# 6_LED_INTERFACE_SFP.net
KiCad netlist of a schematic drawn in Altium Designer
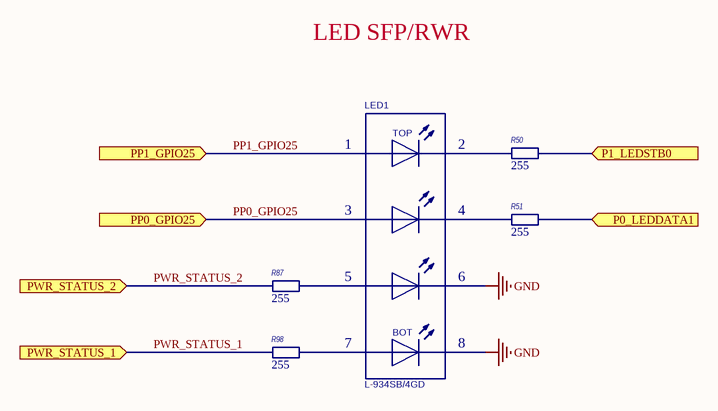
[diagram p0: 6_LED INTERFACE SFP.SchDoc]

(export (version "E")
  (design (tool "Eeschema 10.0.6"))
  (components
    (comp (ref "LED1")
      (value "L-934SB/4GD")
      (footprint "L-934SB/4GD")
      (description "4 LED Green L-934SB/4GD")
      (fields
        (field (name "CUSTOMER PART NUMBER") "Светодиод, 4 LED Green L-934SB/4GD QUAD-LEVEL LED INDICATORS")
        (field (name "MANUFACTURER") "Kingbright")
      )
      (libsource (lib "LED") (part "L-934SB/4GD"))
    )
    (comp (ref "R50")
      (value "ERJ-2RKF2550X")
      (footprint "RESC1005[0402]")
      (description "R0402, 255R 1%")
      (fields
        (field (name "MANUFACTURER") "Panasonic")
        (field (name "TOLERANCE") "±1%")
        (field (name "RESISTANCE (OHMS)") "255")
      )
      (libsource (lib "RESISTOR") (part "ERJ-2RKF2550X"))
    )
    (comp (ref "R51")
      (value "ERJ-2RKF2550X")
      (footprint "RESC1005[0402]")
      (description "R0402, 255R 1%")
      (fields
        (field (name "MANUFACTURER") "Panasonic")
        (field (name "TOLERANCE") "±1%")
        (field (name "RESISTANCE (OHMS)") "255")
      )
      (libsource (lib "RESISTOR") (part "ERJ-2RKF2550X"))
    )
    (comp (ref "R87")
      (value "ERJ-2RKF2550X")
      (footprint "RESC1005[0402]")
      (description "R0402, 255R 1%")
      (fields
        (field (name "MANUFACTURER") "Panasonic")
        (field (name "TOLERANCE") "±1%")
        (field (name "RESISTANCE (OHMS)") "255")
      )
      (libsource (lib "RESISTOR") (part "ERJ-2RKF2550X"))
    )
    (comp (ref "R98")
      (value "ERJ-2RKF2550X")
      (footprint "RESC1005[0402]")
      (description "R0402, 255R 1%")
      (fields
        (field (name "MANUFACTURER") "Panasonic")
        (field (name "TOLERANCE") "±1%")
        (field (name "RESISTANCE (OHMS)") "255")
      )
      (libsource (lib "RESISTOR") (part "ERJ-2RKF2550X"))
    )
  )
  (nets
    (net (code "1") (name "/P0_LEDDATA1") (class "Default") (node (ref "R51") (pin "2") (pintype "passive")))
    (net (code "2") (name "/P1_LEDSTB0") (class "Default") (node (ref "R50") (pin "2") (pintype "passive")))
    (net (code "3") (name "/PP0_GPIO25") (class "Default") (node (ref "LED1") (pin "3") (pintype "passive")))
    (net (code "4") (name "/PP1_GPIO25") (class "Default") (node (ref "LED1") (pin "1") (pintype "passive")))
    (net (code "5") (name "/PWR_STATUS_1") (class "Default") (node (ref "R98") (pin "1") (pintype "passive")))
    (net (code "6") (name "/PWR_STATUS_2") (class "Default") (node (ref "R87") (pin "1") (pintype "passive")))
    (net (code "7") (name "GND") (class "Default")
      (node (ref "LED1") (pin "6") (pintype "passive"))
      (node (ref "LED1") (pin "8") (pintype "passive"))
    )
    (net (code "8") (name "Net-(LED1-Pad2)") (class "Default")
      (node (ref "LED1") (pin "2") (pintype "passive"))
      (node (ref "R50") (pin "1") (pintype "passive"))
    )
    (net (code "9") (name "Net-(LED1-Pad4)") (class "Default")
      (node (ref "LED1") (pin "4") (pintype "passive"))
      (node (ref "R51") (pin "1") (pintype "passive"))
    )
    (net (code "10") (name "Net-(LED1-Pad5)") (class "Default")
      (node (ref "LED1") (pin "5") (pintype "passive"))
      (node (ref "R87") (pin "2") (pintype "passive"))
    )
    (net (code "11") (name "Net-(LED1-Pad7)") (class "Default")
      (node (ref "LED1") (pin "7") (pintype "passive"))
      (node (ref "R98") (pin "2") (pintype "passive"))
    )
  )
)
